# PCB.net
KiCad netlist of a schematic drawn in EAGLE
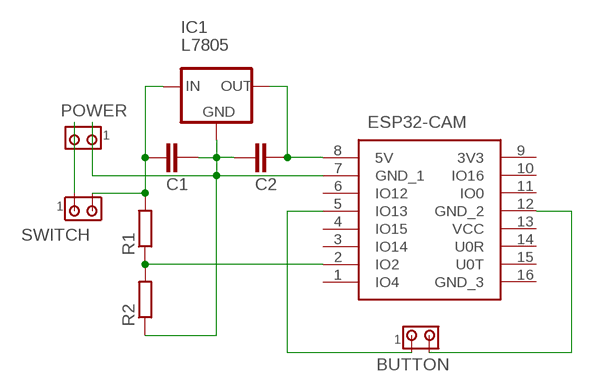
[diagram p0: schematic, sheet 1]

(export (version "E")
  (design (tool "Eeschema 10.0.6"))
  (components
    (comp (ref "BUTTON")
      (value "MTA02-156")
      (footprint "eagle-import:1X2MTA")
      (libsource (lib "eagle-import") (part "MTA02-156"))
    )
    (comp (ref "C1")
      (value "C2,5-3")
      (footprint "eagle-import:C2.5-3")
      (libsource (lib "eagle-import") (part "C2,5-3"))
    )
    (comp (ref "C2")
      (value "C2,5-3")
      (footprint "eagle-import:C2.5-3")
      (libsource (lib "eagle-import") (part "C2,5-3"))
    )
    (comp (ref "IC1")
      (value "L7805")
      (footprint "eagle-import:78XXS")
      (fields (field (name "MF") "STMicroelectronics"))
      (libsource (lib "eagle-import") (part "L7805"))
    )
    (comp (ref "POWER")
      (value "MTA02-156")
      (footprint "eagle-import:1X2MTA")
      (libsource (lib "eagle-import") (part "MTA02-156"))
    )
    (comp (ref "R1")
      (value "R-EU_0207/15")
      (footprint "eagle-import:0207_15")
      (libsource (lib "eagle-import") (part "R-EU_0207/15"))
    )
    (comp (ref "R2")
      (value "R-EU_0207/15")
      (footprint "eagle-import:0207_15")
      (libsource (lib "eagle-import") (part "R-EU_0207/15"))
    )
    (comp (ref "SWITCH")
      (value "MTA02-156")
      (footprint "eagle-import:1X2MTA")
      (libsource (lib "eagle-import") (part "MTA02-156"))
    )
    (comp (ref "U$1")
      (value "ESP32-CAM")
      (footprint "eagle-import:ESP32-CAM")
      (fields (field (name "MF") "AI-Thinker"))
      (libsource (lib "eagle-import") (part "ESP32-CAM"))
    )
  )
  (nets
    (net (code "1") (name "Net-(C1-Pad1)") (class "Default")
      (node (ref "C1") (pin "1") (pinfunction "1_1") (pintype "passive"))
      (node (ref "IC1") (pin "IN") (pinfunction "IN_IN") (pintype "input"))
      (node (ref "R1") (pin "2") (pinfunction "2_2") (pintype "passive"))
      (node (ref "SWITCH") (pin "2") (pinfunction "2_2") (pintype "passive"))
    )
    (net (code "2") (name "Net-(POWER-Pad2)") (class "Default")
      (node (ref "POWER") (pin "2") (pinfunction "2_2") (pintype "passive"))
      (node (ref "SWITCH") (pin "1") (pinfunction "1_1") (pintype "passive"))
    )
    (net (code "3") (name "Net-(U$1-5V)") (class "Default")
      (node (ref "C2") (pin "2") (pinfunction "2_2") (pintype "passive"))
      (node (ref "IC1") (pin "OUT") (pinfunction "OUT_OUT") (pintype "passive"))
      (node (ref "U$1") (pin "8") (pinfunction "5V_8") (pintype "bidirectional"))
    )
    (net (code "4") (name "Net-(U$1-GND_1)") (class "Default")
      (node (ref "C1") (pin "2") (pinfunction "2_2") (pintype "passive"))
      (node (ref "C2") (pin "1") (pinfunction "1_1") (pintype "passive"))
      (node (ref "IC1") (pin "GND") (pinfunction "GND_GND") (pintype "input"))
      (node (ref "POWER") (pin "1") (pinfunction "1_1") (pintype "passive"))
      (node (ref "R2") (pin "1") (pinfunction "1_1") (pintype "passive"))
      (node (ref "U$1") (pin "7") (pinfunction "GND_1_7") (pintype "bidirectional"))
    )
    (net (code "5") (name "Net-(U$1-GND_2)") (class "Default")
      (node (ref "BUTTON") (pin "2") (pinfunction "2_2") (pintype "passive"))
      (node (ref "U$1") (pin "12") (pinfunction "GND_2_12") (pintype "bidirectional"))
    )
    (net (code "6") (name "Net-(U$1-IO2)") (class "Default")
      (node (ref "R1") (pin "1") (pinfunction "1_1") (pintype "passive"))
      (node (ref "R2") (pin "2") (pinfunction "2_2") (pintype "passive"))
      (node (ref "U$1") (pin "2") (pinfunction "IO2_2") (pintype "bidirectional"))
    )
    (net (code "7") (name "Net-(U$1-IO13)") (class "Default")
      (node (ref "BUTTON") (pin "1") (pinfunction "1_1") (pintype "passive"))
      (node (ref "U$1") (pin "5") (pinfunction "IO13_5") (pintype "bidirectional"))
    )
    (net (code "8") (name "unconnected-(U$1-3V3-Pad9)") (class "Default")
      (node (ref "U$1") (pin "9") (pinfunction "3V3_9") (pintype "bidirectional"))
    )
    (net (code "9") (name "unconnected-(U$1-GND_3-Pad16)") (class "Default")
      (node (ref "U$1") (pin "16") (pinfunction "GND_3_16") (pintype "bidirectional"))
    )
    (net (code "10") (name "unconnected-(U$1-IO0-Pad11)") (class "Default")
      (node (ref "U$1") (pin "11") (pinfunction "IO0_11") (pintype "bidirectional"))
    )
    (net (code "11") (name "unconnected-(U$1-IO4-Pad1)") (class "Default")
      (node (ref "U$1") (pin "1") (pinfunction "IO4_1") (pintype "bidirectional"))
    )
    (net (code "12") (name "unconnected-(U$1-IO12-Pad6)") (class "Default")
      (node (ref "U$1") (pin "6") (pinfunction "IO12_6") (pintype "bidirectional"))
    )
    (net (code "13") (name "unconnected-(U$1-IO14-Pad3)") (class "Default")
      (node (ref "U$1") (pin "3") (pinfunction "IO14_3") (pintype "bidirectional"))
    )
    (net (code "14") (name "unconnected-(U$1-IO15-Pad4)") (class "Default")
      (node (ref "U$1") (pin "4") (pinfunction "IO15_4") (pintype "bidirectional"))
    )
    (net (code "15") (name "unconnected-(U$1-IO16-Pad10)") (class "Default")
      (node (ref "U$1") (pin "10") (pinfunction "IO16_10") (pintype "bidirectional"))
    )
    (net (code "16") (name "unconnected-(U$1-U0R-Pad14)") (class "Default")
      (node (ref "U$1") (pin "14") (pinfunction "U0R_14") (pintype "bidirectional"))
    )
    (net (code "17") (name "unconnected-(U$1-U0T-Pad15)") (class "Default")
      (node (ref "U$1") (pin "15") (pinfunction "U0T_15") (pintype "bidirectional"))
    )
    (net (code "18") (name "unconnected-(U$1-VCC-Pad13)") (class "Default")
      (node (ref "U$1") (pin "13") (pinfunction "VCC_13") (pintype "bidirectional"))
    )
  )
)
